# RFM69HCW.net
KiCad netlist of a schematic drawn in EAGLE
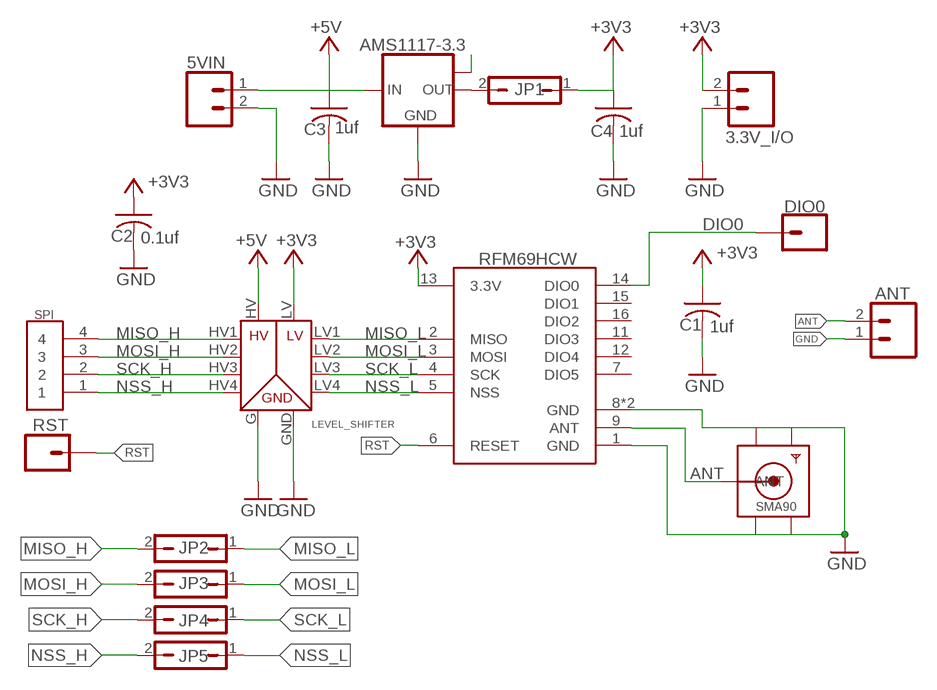
[diagram p0: schematic, sheet 1]

(export (version "E")
  (design (tool "Eeschema 10.0.6"))
  (components
    (comp (ref "3.3V_I/O")
      (value "M021X02_NO_SILK")
      (footprint "eagle-import:1X02_NO_SILK")
      (libsource (lib "eagle-import") (part "M021X02_NO_SILK"))
    )
    (comp (ref "5VIN")
      (value "M021X02_NO_SILK")
      (footprint "eagle-import:1X02_NO_SILK")
      (libsource (lib "eagle-import") (part "M021X02_NO_SILK"))
    )
    (comp (ref "AMS1117-3.3")
      (value "LM1117MPX-1.8")
      (footprint "eagle-import:SOT223")
      (libsource (lib "eagle-import") (part "LM1117MPX-1.8"))
    )
    (comp (ref "ANT")
      (value "M021X02_NO_SILK")
      (footprint "eagle-import:1X02_NO_SILK")
      (libsource (lib "eagle-import") (part "M021X02_NO_SILK"))
    )
    (comp (ref "C1")
      (value "1uf")
      (footprint "eagle-import:C0805")
      (libsource (lib "eagle-import") (part "C-USC0805"))
    )
    (comp (ref "C2")
      (value "0.1uf")
      (footprint "eagle-import:C0805")
      (libsource (lib "eagle-import") (part "C-USC0805"))
    )
    (comp (ref "C3")
      (value "1uf")
      (footprint "eagle-import:C0805")
      (libsource (lib "eagle-import") (part "C-USC0805"))
    )
    (comp (ref "C4")
      (value "1uf")
      (footprint "eagle-import:C0805")
      (libsource (lib "eagle-import") (part "C-USC0805"))
    )
    (comp (ref "DIO0")
      (value "M01SMDNS")
      (footprint "eagle-import:1X01NS")
      (libsource (lib "eagle-import") (part "M01SMDNS"))
    )
    (comp (ref "JP1")
      (value "JP1Q")
      (footprint "eagle-import:JP1")
      (libsource (lib "eagle-import") (part "JP1Q"))
    )
    (comp (ref "JP2")
      (value "JP1Q")
      (footprint "eagle-import:JP1")
      (libsource (lib "eagle-import") (part "JP1Q"))
    )
    (comp (ref "JP3")
      (value "JP1Q")
      (footprint "eagle-import:JP1")
      (libsource (lib "eagle-import") (part "JP1Q"))
    )
    (comp (ref "JP4")
      (value "JP1Q")
      (footprint "eagle-import:JP1")
      (libsource (lib "eagle-import") (part "JP1Q"))
    )
    (comp (ref "JP5")
      (value "JP1Q")
      (footprint "eagle-import:JP1")
      (libsource (lib "eagle-import") (part "JP1Q"))
    )
    (comp (ref "RST")
      (value "M01SMDNS")
      (footprint "eagle-import:1X01NS")
      (libsource (lib "eagle-import") (part "M01SMDNS"))
    )
    (comp (ref "SMA90")
      (value "SMACONNECTOR_EDGE")
      (footprint "eagle-import:SMA_EDGELAUNCH")
      (libsource (lib "eagle-import") (part "SMACONNECTOR_EDGE"))
    )
    (comp (ref "SPI")
      (value "1X4-CLEANBIG")
      (footprint "eagle-import:1X04-CLEANBIG")
      (libsource (lib "eagle-import") (part "1X4-CLEANBIG"))
    )
    (comp (ref "U$1")
      (value "LEVEL_SHIFTER")
      (footprint "eagle-import:LEVEL_SHIFTER")
      (libsource (lib "eagle-import") (part "LEVEL_SHIFTER"))
    )
    (comp (ref "U1")
      (value "RFM69HCW")
      (footprint "eagle-import:RFM69HCW-XXXS2")
      (libsource (lib "eagle-import") (part "RFM69HCW"))
    )
  )
  (nets
    (net (code "1") (name "+3V3") (class "Default")
      (node (ref "3.3V_I/O") (pin "2") (pinfunction "2_2") (pintype "passive"))
      (node (ref "C1") (pin "1") (pinfunction "1_1") (pintype "passive"))
      (node (ref "C2") (pin "1") (pinfunction "1_1") (pintype "passive"))
      (node (ref "C4") (pin "1") (pinfunction "1_1") (pintype "passive"))
      (node (ref "JP1") (pin "1") (pinfunction "1_1") (pintype "passive"))
      (node (ref "U$1") (pin "LV") (pinfunction "LV_LV") (pintype "bidirectional"))
      (node (ref "U1") (pin "13") (pinfunction "3.3V_13") (pintype "power_in"))
    )
    (net (code "2") (name "+5V") (class "Default")
      (node (ref "5VIN") (pin "1") (pinfunction "1_1") (pintype "passive"))
      (node (ref "AMS1117-3.3") (pin "3") (pinfunction "IN_3") (pintype "input"))
      (node (ref "C3") (pin "1") (pinfunction "1_1") (pintype "passive"))
      (node (ref "U$1") (pin "HV") (pinfunction "HV_HV") (pintype "bidirectional"))
    )
    (net (code "3") (name "/DIO0") (class "Default")
      (node (ref "DIO0") (pin "1") (pinfunction "1_1") (pintype "passive"))
      (node (ref "U1") (pin "14") (pinfunction "DIO0_14") (pintype "bidirectional"))
    )
    (net (code "4") (name "ANT") (class "Default")
      (node (ref "ANT") (pin "2") (pinfunction "2_2") (pintype "passive"))
      (node (ref "SMA90") (pin "P") (pinfunction "ANT_P") (pintype "bidirectional"))
      (node (ref "U1") (pin "9") (pinfunction "ANT_9") (pintype "passive"))
    )
    (net (code "5") (name "GND") (class "Default")
      (node (ref "3.3V_I/O") (pin "1") (pinfunction "1_1") (pintype "passive"))
      (node (ref "5VIN") (pin "2") (pinfunction "2_2") (pintype "passive"))
      (node (ref "AMS1117-3.3") (pin "1") (pinfunction "GND_1") (pintype "input"))
      (node (ref "ANT") (pin "1") (pinfunction "1_1") (pintype "passive"))
      (node (ref "C1") (pin "2") (pinfunction "2_2") (pintype "passive"))
      (node (ref "C2") (pin "2") (pinfunction "2_2") (pintype "passive"))
      (node (ref "C3") (pin "2") (pinfunction "2_2") (pintype "passive"))
      (node (ref "C4") (pin "2") (pinfunction "2_2") (pintype "passive"))
      (node (ref "SMA90") (pin "GND@1") (pinfunction "GND4_GND@1") (pintype "power_in"))
      (node (ref "SMA90") (pin "GND@2") (pinfunction "GND3_GND@2") (pintype "power_in"))
      (node (ref "SMA90") (pin "GND@3") (pinfunction "GND2_GND@3") (pintype "power_in"))
      (node (ref "SMA90") (pin "GND@4") (pinfunction "GND1_GND@4") (pintype "power_in"))
      (node (ref "U$1") (pin "G") (pinfunction "GND_G") (pintype "bidirectional"))
      (node (ref "U$1") (pin "GND") (pinfunction "GND1_GND") (pintype "bidirectional"))
      (node (ref "U1") (pin "1") (pinfunction "GND_1") (pintype "power_in"))
      (node (ref "U1") (pin "10") (pinfunction "GND_10") (pintype "power_in"))
      (node (ref "U1") (pin "8") (pinfunction "GND_8") (pintype "power_in"))
    )
    (net (code "6") (name "MISO_H") (class "Default")
      (node (ref "JP2") (pin "2") (pinfunction "2_2") (pintype "passive"))
      (node (ref "SPI") (pin "4") (pinfunction "4_4") (pintype "bidirectional"))
      (node (ref "U$1") (pin "HV1") (pinfunction "HV1_HV1") (pintype "bidirectional"))
    )
    (net (code "7") (name "MISO_L") (class "Default")
      (node (ref "JP2") (pin "1") (pinfunction "1_1") (pintype "passive"))
      (node (ref "U$1") (pin "LV1") (pinfunction "LV1_LV1") (pintype "bidirectional"))
      (node (ref "U1") (pin "2") (pinfunction "MISO_2") (pintype "bidirectional"))
    )
    (net (code "8") (name "MOSI_H") (class "Default")
      (node (ref "JP3") (pin "2") (pinfunction "2_2") (pintype "passive"))
      (node (ref "SPI") (pin "3") (pinfunction "3_3") (pintype "bidirectional"))
      (node (ref "U$1") (pin "HV2") (pinfunction "HV2_HV2") (pintype "bidirectional"))
    )
    (net (code "9") (name "MOSI_L") (class "Default")
      (node (ref "JP3") (pin "1") (pinfunction "1_1") (pintype "passive"))
      (node (ref "U$1") (pin "LV2") (pinfunction "LV2_LV2") (pintype "bidirectional"))
      (node (ref "U1") (pin "3") (pinfunction "MOSI_3") (pintype "input"))
    )
    (net (code "10") (name "NSS_H") (class "Default")
      (node (ref "JP5") (pin "2") (pinfunction "2_2") (pintype "passive"))
      (node (ref "SPI") (pin "1") (pinfunction "1_1") (pintype "bidirectional"))
      (node (ref "U$1") (pin "HV4") (pinfunction "HV4_HV4") (pintype "bidirectional"))
    )
    (net (code "11") (name "NSS_L") (class "Default")
      (node (ref "JP5") (pin "1") (pinfunction "1_1") (pintype "passive"))
      (node (ref "U$1") (pin "LV4") (pinfunction "LV4_LV4") (pintype "bidirectional"))
      (node (ref "U1") (pin "5") (pinfunction "NSS_5") (pintype "input"))
    )
    (net (code "12") (name "Net-(AMS1117-3.3-OUT)") (class "Default")
      (node (ref "AMS1117-3.3") (pin "2") (pinfunction "OUT_2") (pintype "passive"))
      (node (ref "JP1") (pin "2") (pinfunction "2_2") (pintype "passive"))
    )
    (net (code "13") (name "RST") (class "Default")
      (node (ref "RST") (pin "1") (pinfunction "1_1") (pintype "passive"))
      (node (ref "U1") (pin "6") (pinfunction "RESET_6") (pintype "input"))
    )
    (net (code "14") (name "SCK_H") (class "Default")
      (node (ref "JP4") (pin "2") (pinfunction "2_2") (pintype "passive"))
      (node (ref "SPI") (pin "2") (pinfunction "2_2") (pintype "bidirectional"))
      (node (ref "U$1") (pin "HV3") (pinfunction "HV3_HV3") (pintype "bidirectional"))
    )
    (net (code "15") (name "SCK_L") (class "Default")
      (node (ref "JP4") (pin "1") (pinfunction "1_1") (pintype "passive"))
      (node (ref "U$1") (pin "LV3") (pinfunction "LV3_LV3") (pintype "bidirectional"))
      (node (ref "U1") (pin "4") (pinfunction "SCK_4") (pintype "input"))
    )
    (net (code "16") (name "unconnected-(AMS1117-3.3-OUT1-PadTAB)") (class "Default")
      (node (ref "AMS1117-3.3") (pin "TAB") (pinfunction "OUT1_TAB") (pintype "passive"))
    )
    (net (code "17") (name "unconnected-(U1-DIO1-Pad15)") (class "Default")
      (node (ref "U1") (pin "15") (pinfunction "DIO1_15") (pintype "bidirectional"))
    )
    (net (code "18") (name "unconnected-(U1-DIO2-Pad16)") (class "Default")
      (node (ref "U1") (pin "16") (pinfunction "DIO2_16") (pintype "bidirectional"))
    )
    (net (code "19") (name "unconnected-(U1-DIO3-Pad11)") (class "Default")
      (node (ref "U1") (pin "11") (pinfunction "DIO3_11") (pintype "bidirectional"))
    )
    (net (code "20") (name "unconnected-(U1-DIO4-Pad12)") (class "Default")
      (node (ref "U1") (pin "12") (pinfunction "DIO4_12") (pintype "bidirectional"))
    )
    (net (code "21") (name "unconnected-(U1-DIO5-Pad7)") (class "Default")
      (node (ref "U1") (pin "7") (pinfunction "DIO5_7") (pintype "bidirectional"))
    )
  )
)
